# Sheet1.net
KiCad netlist of a schematic drawn in Altium Designer
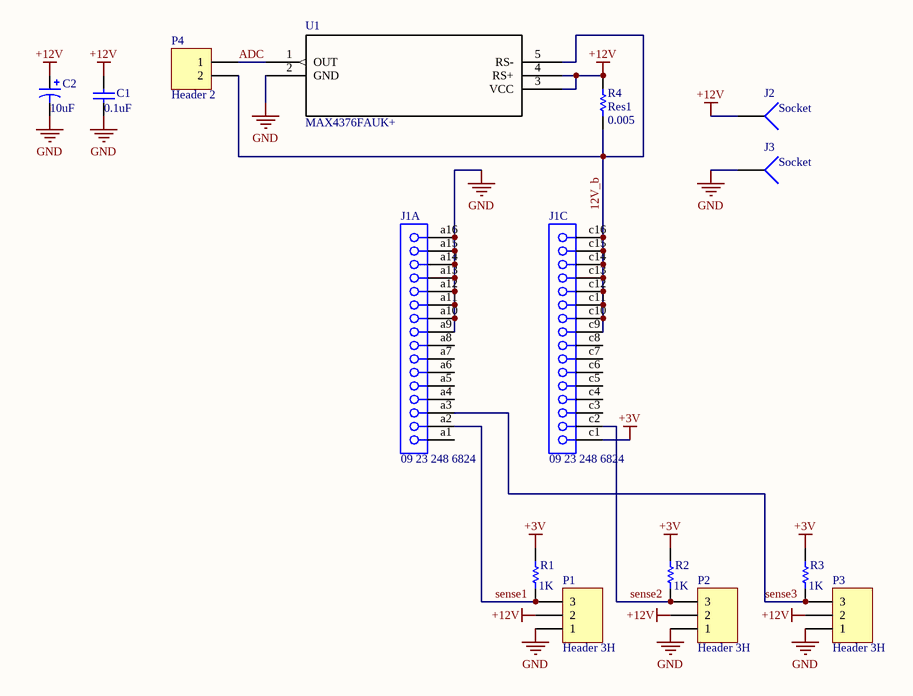
[diagram p0: Sheet1.SchDoc]

(export (version "E")
  (design (tool "Eeschema 10.0.6"))
  (components
    (comp (ref "C1")
      (value "0.1uF")
      (footprint "C0805")
      (description "Capacitor (Semiconductor SIM Model)")
      (fields (field (name "Comment") "Cap") (field (name "PUBLISHER") "Altium Limited"))
      (libsource (lib "Miscellaneous Devices") (part "Cap Semi"))
    )
    (comp (ref "C2")
      (value "10uF")
      (footprint "C1210_N")
      (description "Polarized Capacitor (Radial)")
      (fields (field (name "Comment") "Cap Pol1") (field (name "PUBLISHER") "Altium Limited"))
      (libsource (lib "Miscellaneous Devices") (part "Cap Pol1"))
    )
    (comp (ref "J1")
      (value "09 23 248 6824")
      (footprint "0923248x824")
      (fields (field (name "PUBLISHER") "Altium Limited"))
      (libsource (lib "HARTING DIN 41612 Type 2C") (part "09 23 248 6824"))
    )
    (comp (ref "J2")
      (value "Socket")
      (footprint "PIN1")
      (fields (field (name "PUBLISHER") "Altium Limited"))
      (libsource (lib "Miscellaneous Connectors") (part "Socket"))
    )
    (comp (ref "J3")
      (value "Socket")
      (footprint "PIN1")
      (fields (field (name "PUBLISHER") "Altium Limited"))
      (libsource (lib "Miscellaneous Connectors") (part "Socket"))
    )
    (comp (ref "P1")
      (value "Header 3H")
      (footprint "HDR1X3H")
      (description "Header, 3-Pin, Right Angle")
      (fields (field (name "PUBLISHER") "Altium Limited"))
      (libsource (lib "Miscellaneous Connectors") (part "Header 3H"))
    )
    (comp (ref "P2")
      (value "Header 3H")
      (footprint "HDR1X3H")
      (description "Header, 3-Pin, Right Angle")
      (fields (field (name "PUBLISHER") "Altium Limited"))
      (libsource (lib "Miscellaneous Connectors") (part "Header 3H"))
    )
    (comp (ref "P3")
      (value "Header 3H")
      (footprint "HDR1X3H")
      (description "Header, 3-Pin, Right Angle")
      (fields (field (name "PUBLISHER") "Altium Limited"))
      (libsource (lib "Miscellaneous Connectors") (part "Header 3H"))
    )
    (comp (ref "P4")
      (value "Header 2")
      (footprint "HDR1X2")
      (description "Header, 2-Pin")
      (fields (field (name "PUBLISHER") "Altium Limited"))
      (libsource (lib "Miscellaneous Connectors") (part "Header 2"))
    )
    (comp (ref "R1")
      (value "1K")
      (footprint "AXIAL-0.3")
      (description "Resistor")
      (fields (field (name "Comment") "Res1") (field (name "PUBLISHER") "Altium Limited"))
      (libsource (lib "Miscellaneous Devices") (part "Res1"))
    )
    (comp (ref "R2")
      (value "1K")
      (footprint "AXIAL-0.3")
      (description "Resistor")
      (fields (field (name "Comment") "Res1") (field (name "PUBLISHER") "Altium Limited"))
      (libsource (lib "Miscellaneous Devices") (part "Res1"))
    )
    (comp (ref "R3")
      (value "1K")
      (footprint "AXIAL-0.3")
      (description "Resistor")
      (fields (field (name "Comment") "Res1") (field (name "PUBLISHER") "Altium Limited"))
      (libsource (lib "Miscellaneous Devices") (part "Res1"))
    )
    (comp (ref "R4")
      (value "Res1")
      (footprint "C1206")
      (description "Resistor")
      (fields (field (name "ALTIUM_VALUE") "0.005") (field (name "PUBLISHER") "Altium Limited"))
      (libsource (lib "Miscellaneous Devices") (part "Res1"))
    )
    (comp (ref "U1")
      (value "MAX4376FAUK+")
      (footprint "21-0057F")
      (description "Imported")
      (fields (field (name "MANUFACTURER_PART_NUMBER") "max4376fauk+"))
      (libsource (lib "Schlib") (part "MAX4376FAUK+"))
    )
  )
  (nets
    (net (code "1") (name "+3V") (class "Default")
      (node (ref "J1") (pin "c1") (pinfunction "c1_c1") (pintype "passive"))
      (node (ref "R1") (pin "2") (pinfunction "2_2") (pintype "passive"))
      (node (ref "R2") (pin "2") (pinfunction "2_2") (pintype "passive"))
      (node (ref "R3") (pin "2") (pinfunction "2_2") (pintype "passive"))
    )
    (net (code "2") (name "+12V") (class "Default")
      (node (ref "C1") (pin "2") (pinfunction "2_2") (pintype "passive"))
      (node (ref "C2") (pin "1") (pinfunction "1_1") (pintype "passive"))
      (node (ref "J2") (pin "1") (pinfunction "1_1") (pintype "passive"))
      (node (ref "P1") (pin "2") (pinfunction "2_2") (pintype "passive"))
      (node (ref "P2") (pin "2") (pinfunction "2_2") (pintype "passive"))
      (node (ref "P3") (pin "2") (pinfunction "2_2") (pintype "passive"))
      (node (ref "R4") (pin "2") (pinfunction "2_2") (pintype "passive"))
      (node (ref "U1") (pin "3") (pinfunction "VCC_3") (pintype "power_in"))
      (node (ref "U1") (pin "4") (pinfunction "RS+_4") (pintype "passive"))
    )
    (net (code "3") (name "/12V_b") (class "Default")
      (node (ref "J1") (pin "c10") (pinfunction "c10_c10") (pintype "passive"))
      (node (ref "J1") (pin "c11") (pinfunction "c11_c11") (pintype "passive"))
      (node (ref "J1") (pin "c12") (pinfunction "c12_c12") (pintype "passive"))
      (node (ref "J1") (pin "c13") (pinfunction "c13_c13") (pintype "passive"))
      (node (ref "J1") (pin "c14") (pinfunction "c14_c14") (pintype "passive"))
      (node (ref "J1") (pin "c15") (pinfunction "c15_c15") (pintype "passive"))
      (node (ref "J1") (pin "c16") (pinfunction "c16_c16") (pintype "passive"))
      (node (ref "J1") (pin "c9") (pinfunction "c9_c9") (pintype "passive"))
      (node (ref "P4") (pin "2") (pinfunction "2_2") (pintype "passive"))
      (node (ref "R4") (pin "1") (pinfunction "1_1") (pintype "passive"))
      (node (ref "U1") (pin "5") (pinfunction "RS-_5") (pintype "passive"))
    )
    (net (code "4") (name "/ADC") (class "Default")
      (node (ref "P4") (pin "1") (pinfunction "1_1") (pintype "passive"))
      (node (ref "U1") (pin "1") (pinfunction "OUT_1") (pintype "output"))
    )
    (net (code "5") (name "/sense1") (class "Default")
      (node (ref "J1") (pin "a2") (pinfunction "a2_a2") (pintype "passive"))
      (node (ref "P1") (pin "3") (pinfunction "3_3") (pintype "passive"))
      (node (ref "R1") (pin "1") (pinfunction "1_1") (pintype "passive"))
    )
    (net (code "6") (name "/sense2") (class "Default")
      (node (ref "J1") (pin "c2") (pinfunction "c2_c2") (pintype "passive"))
      (node (ref "P2") (pin "3") (pinfunction "3_3") (pintype "passive"))
      (node (ref "R2") (pin "1") (pinfunction "1_1") (pintype "passive"))
    )
    (net (code "7") (name "/sense3") (class "Default")
      (node (ref "J1") (pin "a3") (pinfunction "a3_a3") (pintype "passive"))
      (node (ref "P3") (pin "3") (pinfunction "3_3") (pintype "passive"))
      (node (ref "R3") (pin "1") (pinfunction "1_1") (pintype "passive"))
    )
    (net (code "8") (name "GND") (class "Default")
      (node (ref "C1") (pin "1") (pinfunction "1_1") (pintype "passive"))
      (node (ref "C2") (pin "2") (pinfunction "2_2") (pintype "passive"))
      (node (ref "J1") (pin "a10") (pinfunction "a10_a10") (pintype "passive"))
      (node (ref "J1") (pin "a11") (pinfunction "a11_a11") (pintype "passive"))
      (node (ref "J1") (pin "a12") (pinfunction "a12_a12") (pintype "passive"))
      (node (ref "J1") (pin "a13") (pinfunction "a13_a13") (pintype "passive"))
      (node (ref "J1") (pin "a14") (pinfunction "a14_a14") (pintype "passive"))
      (node (ref "J1") (pin "a15") (pinfunction "a15_a15") (pintype "passive"))
      (node (ref "J1") (pin "a16") (pinfunction "a16_a16") (pintype "passive"))
      (node (ref "J1") (pin "a9") (pinfunction "a9_a9") (pintype "passive"))
      (node (ref "J3") (pin "1") (pinfunction "1_1") (pintype "passive"))
      (node (ref "P1") (pin "1") (pinfunction "1_1") (pintype "passive"))
      (node (ref "P2") (pin "1") (pinfunction "1_1") (pintype "passive"))
      (node (ref "P3") (pin "1") (pinfunction "1_1") (pintype "passive"))
      (node (ref "U1") (pin "2") (pinfunction "GND_2") (pintype "power_in"))
    )
    (net (code "9") (name "unconnected-(J1-Pada1)") (class "Default")
      (node (ref "J1") (pin "a1") (pinfunction "a1_a1") (pintype "passive"))
    )
    (net (code "10") (name "unconnected-(J1-Pada4)") (class "Default")
      (node (ref "J1") (pin "a4") (pinfunction "a4_a4") (pintype "passive"))
    )
    (net (code "11") (name "unconnected-(J1-Pada5)") (class "Default")
      (node (ref "J1") (pin "a5") (pinfunction "a5_a5") (pintype "passive"))
    )
    (net (code "12") (name "unconnected-(J1-Pada6)") (class "Default")
      (node (ref "J1") (pin "a6") (pinfunction "a6_a6") (pintype "passive"))
    )
    (net (code "13") (name "unconnected-(J1-Pada7)") (class "Default")
      (node (ref "J1") (pin "a7") (pinfunction "a7_a7") (pintype "passive"))
    )
    (net (code "14") (name "unconnected-(J1-Pada8)") (class "Default")
      (node (ref "J1") (pin "a8") (pinfunction "a8_a8") (pintype "passive"))
    )
    (net (code "15") (name "unconnected-(J1-Padc3)") (class "Default")
      (node (ref "J1") (pin "c3") (pinfunction "c3_c3") (pintype "passive"))
    )
    (net (code "16") (name "unconnected-(J1-Padc4)") (class "Default")
      (node (ref "J1") (pin "c4") (pinfunction "c4_c4") (pintype "passive"))
    )
    (net (code "17") (name "unconnected-(J1-Padc5)") (class "Default")
      (node (ref "J1") (pin "c5") (pinfunction "c5_c5") (pintype "passive"))
    )
    (net (code "18") (name "unconnected-(J1-Padc6)") (class "Default")
      (node (ref "J1") (pin "c6") (pinfunction "c6_c6") (pintype "passive"))
    )
    (net (code "19") (name "unconnected-(J1-Padc7)") (class "Default")
      (node (ref "J1") (pin "c7") (pinfunction "c7_c7") (pintype "passive"))
    )
    (net (code "20") (name "unconnected-(J1-Padc8)") (class "Default")
      (node (ref "J1") (pin "c8") (pinfunction "c8_c8") (pintype "passive"))
    )
  )
)
